# BMS-Sch.net
KiCad netlist of a schematic drawn in Altium Designer
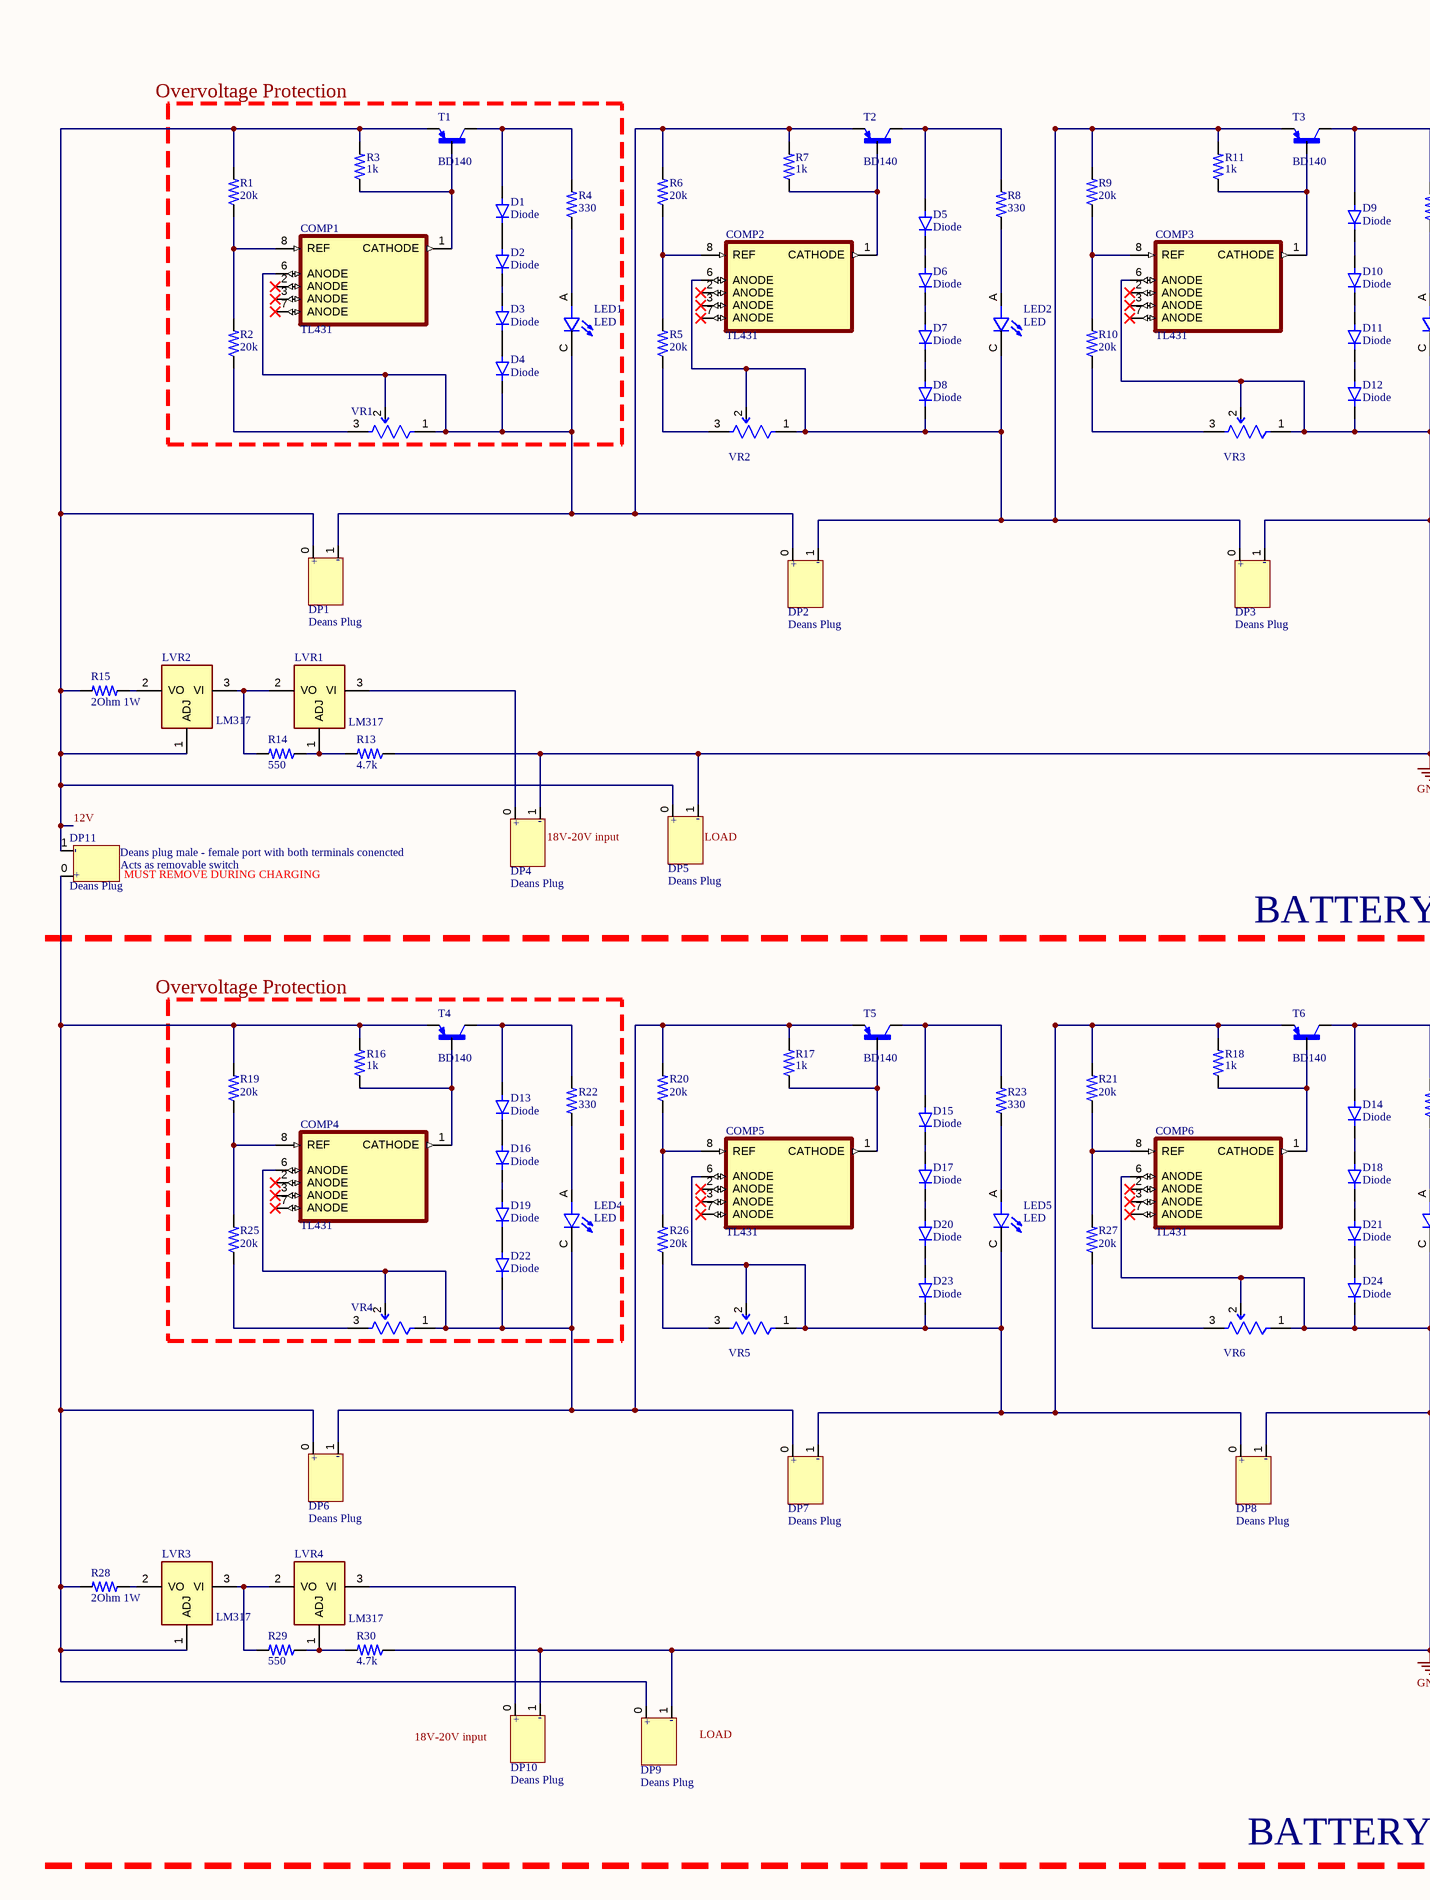
[diagram p0: BMS-Sch.SchDoc, left]
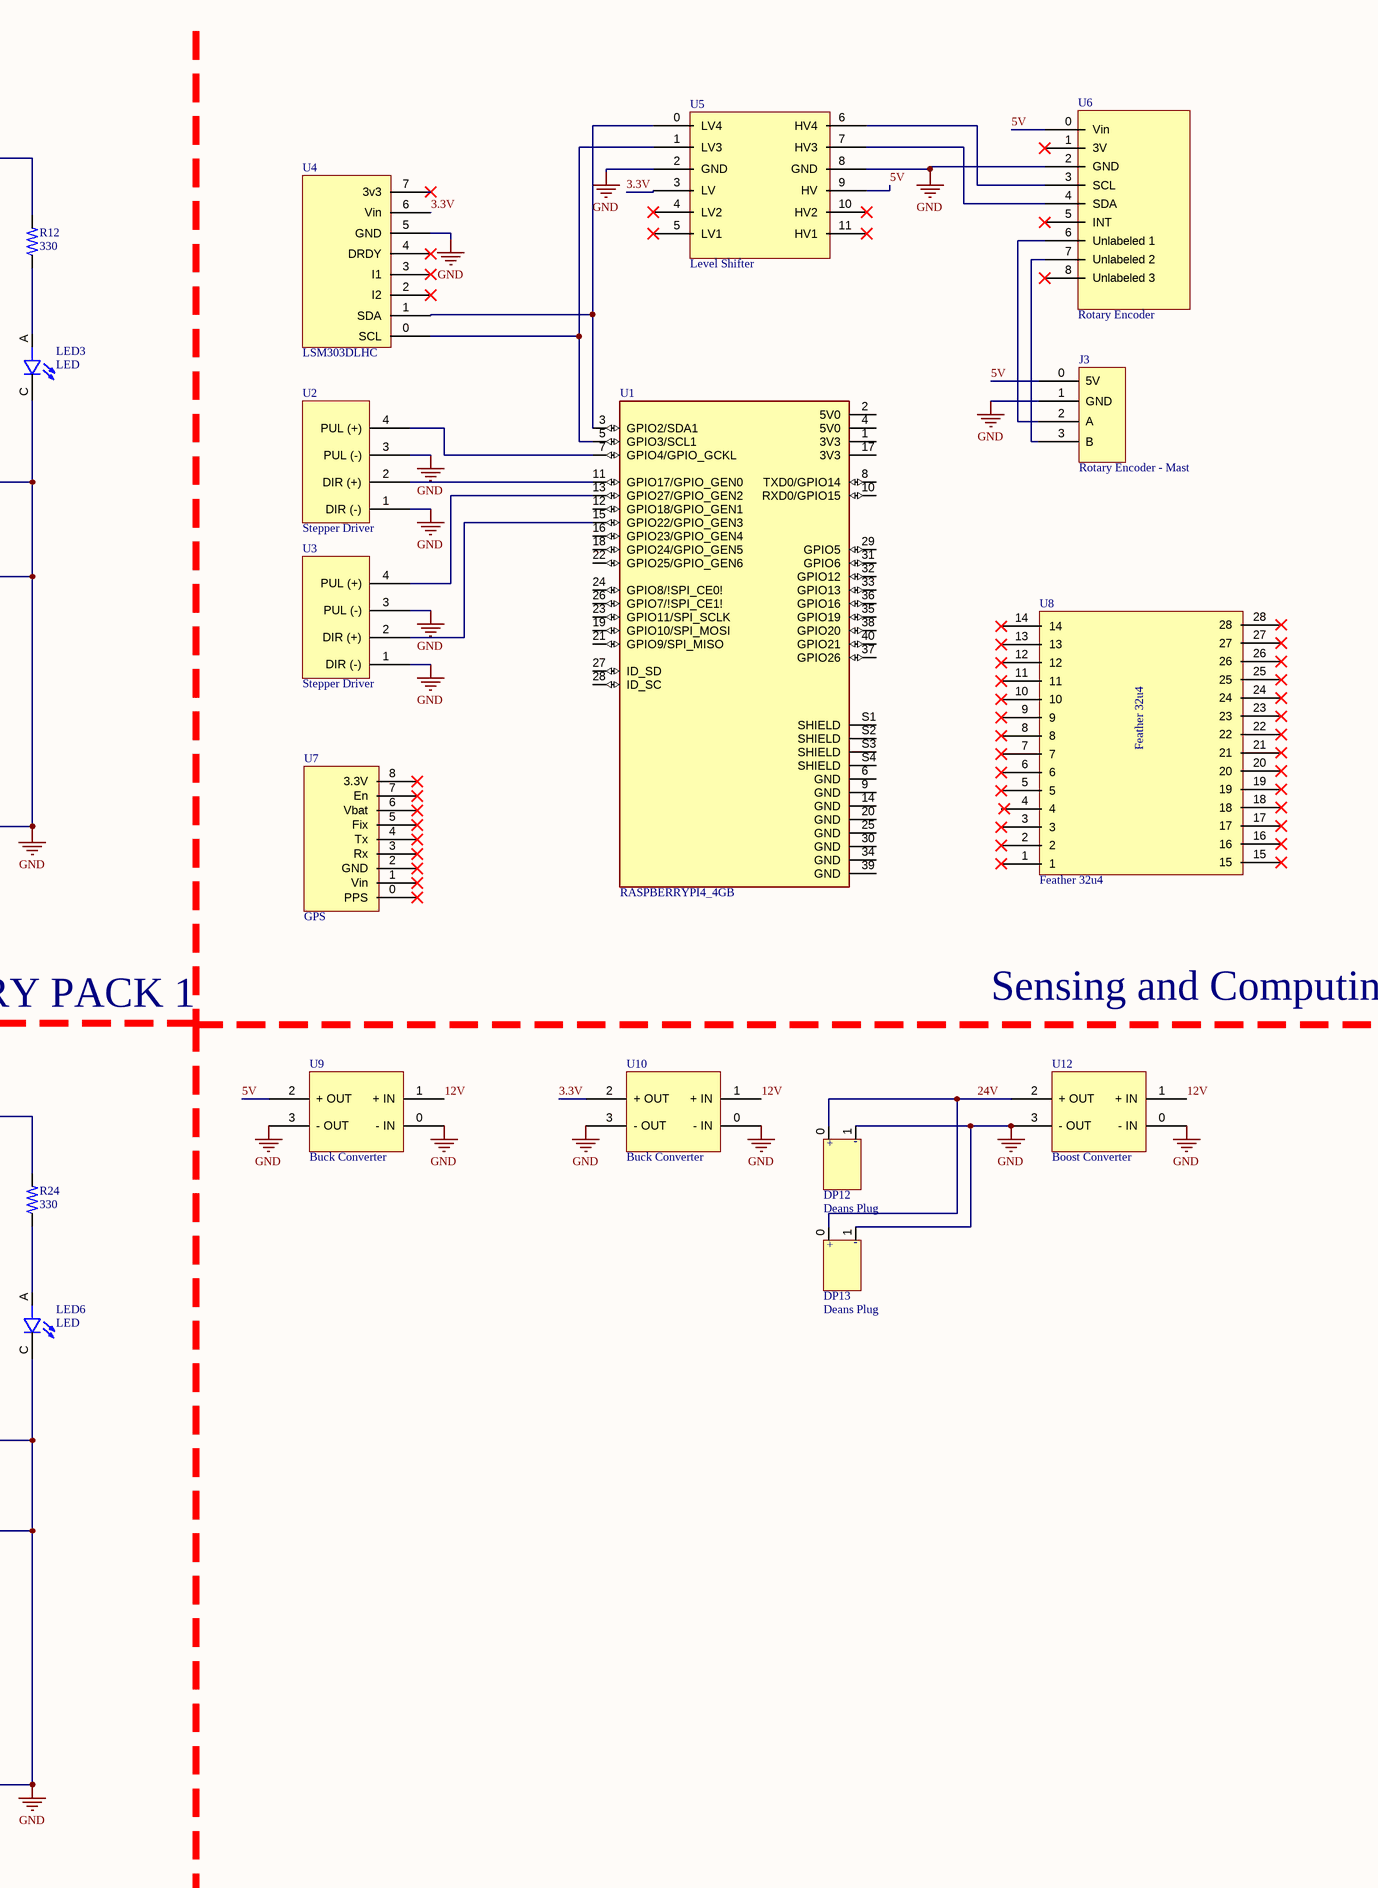
[diagram p1: BMS-Sch.SchDoc, right]

(export (version "E")
  (design (tool "Eeschema 10.0.6"))
  (components
    (comp (ref "COMP1")
      (value "TL431")
      (footprint "SOIC127P599X175-8N")
      (description "Adjustable precision shunt regulator 8-SOIC 0 to 70")
      (fields (field (name "MF") "Texas Instruments") (field (name "MP") "TL431CD"))
      (libsource (lib "Schlib") (part "TL431"))
    )
    (comp (ref "COMP2")
      (value "TL431")
      (footprint "SOIC127P599X175-8N")
      (description "Adjustable precision shunt regulator 8-SOIC 0 to 70")
      (fields (field (name "MF") "Texas Instruments") (field (name "MP") "TL431CD"))
      (libsource (lib "Schlib") (part "TL431"))
    )
    (comp (ref "COMP3")
      (value "TL431")
      (footprint "SOIC127P599X175-8N")
      (description "Adjustable precision shunt regulator 8-SOIC 0 to 70")
      (fields (field (name "MF") "Texas Instruments") (field (name "MP") "TL431CD"))
      (libsource (lib "Schlib") (part "TL431"))
    )
    (comp (ref "COMP4")
      (value "TL431")
      (footprint "SOIC127P599X175-8N")
      (description "Adjustable precision shunt regulator 8-SOIC 0 to 70")
      (fields (field (name "MF") "Texas Instruments") (field (name "MP") "TL431CD"))
      (libsource (lib "Schlib") (part "TL431"))
    )
    (comp (ref "COMP5")
      (value "TL431")
      (footprint "SOIC127P599X175-8N")
      (description "Adjustable precision shunt regulator 8-SOIC 0 to 70")
      (fields (field (name "MF") "Texas Instruments") (field (name "MP") "TL431CD"))
      (libsource (lib "Schlib") (part "TL431"))
    )
    (comp (ref "COMP6")
      (value "TL431")
      (footprint "SOIC127P599X175-8N")
      (description "Adjustable precision shunt regulator 8-SOIC 0 to 70")
      (fields (field (name "MF") "Texas Instruments") (field (name "MP") "TL431CD"))
      (libsource (lib "Schlib") (part "TL431"))
    )
    (comp (ref "D1")
      (value "Diode")
      (footprint "DIOAD1060W80L520D270")
      (description "Diode Standard 1000V 1A Through Hole DO-204AL _DO-41_")
      (fields (field (name "MF") "ON Semiconductor") (field (name "MP") "1N4007"))
      (libsource (lib "Schlib") (part "Diode"))
    )
    (comp (ref "D2")
      (value "Diode")
      (footprint "DIOAD1060W80L520D270")
      (description "Diode Standard 1000V 1A Through Hole DO-204AL _DO-41_")
      (fields (field (name "MF") "ON Semiconductor") (field (name "MP") "1N4007"))
      (libsource (lib "Schlib") (part "Diode"))
    )
    (comp (ref "D3")
      (value "Diode")
      (footprint "DIOAD1060W80L520D270")
      (description "Diode Standard 1000V 1A Through Hole DO-204AL _DO-41_")
      (fields (field (name "MF") "ON Semiconductor") (field (name "MP") "1N4007"))
      (libsource (lib "Schlib") (part "Diode"))
    )
    (comp (ref "D4")
      (value "Diode")
      (footprint "DIOAD1060W80L520D270")
      (description "Diode Standard 1000V 1A Through Hole DO-204AL _DO-41_")
      (fields (field (name "MF") "ON Semiconductor") (field (name "MP") "1N4007"))
      (libsource (lib "Schlib") (part "Diode"))
    )
    (comp (ref "D5")
      (value "Diode")
      (footprint "DIOAD1060W80L520D270")
      (description "Diode Standard 1000V 1A Through Hole DO-204AL _DO-41_")
      (fields (field (name "MF") "ON Semiconductor") (field (name "MP") "1N4007"))
      (libsource (lib "Schlib") (part "Diode"))
    )
    (comp (ref "D6")
      (value "Diode")
      (footprint "DIOAD1060W80L520D270")
      (description "Diode Standard 1000V 1A Through Hole DO-204AL _DO-41_")
      (fields (field (name "MF") "ON Semiconductor") (field (name "MP") "1N4007"))
      (libsource (lib "Schlib") (part "Diode"))
    )
    (comp (ref "D7")
      (value "Diode")
      (footprint "DIOAD1060W80L520D270")
      (description "Diode Standard 1000V 1A Through Hole DO-204AL _DO-41_")
      (fields (field (name "MF") "ON Semiconductor") (field (name "MP") "1N4007"))
      (libsource (lib "Schlib") (part "Diode"))
    )
    (comp (ref "D8")
      (value "Diode")
      (footprint "DIOAD1060W80L520D270")
      (description "Diode Standard 1000V 1A Through Hole DO-204AL _DO-41_")
      (fields (field (name "MF") "ON Semiconductor") (field (name "MP") "1N4007"))
      (libsource (lib "Schlib") (part "Diode"))
    )
    (comp (ref "D9")
      (value "Diode")
      (footprint "DIOAD1060W80L520D270")
      (description "Diode Standard 1000V 1A Through Hole DO-204AL _DO-41_")
      (fields (field (name "MF") "ON Semiconductor") (field (name "MP") "1N4007"))
      (libsource (lib "Schlib") (part "Diode"))
    )
    (comp (ref "D10")
      (value "Diode")
      (footprint "DIOAD1060W80L520D270")
      (description "Diode Standard 1000V 1A Through Hole DO-204AL _DO-41_")
      (fields (field (name "MF") "ON Semiconductor") (field (name "MP") "1N4007"))
      (libsource (lib "Schlib") (part "Diode"))
    )
    (comp (ref "D11")
      (value "Diode")
      (footprint "DIOAD1060W80L520D270")
      (description "Diode Standard 1000V 1A Through Hole DO-204AL _DO-41_")
      (fields (field (name "MF") "ON Semiconductor") (field (name "MP") "1N4007"))
      (libsource (lib "Schlib") (part "Diode"))
    )
    (comp (ref "D12")
      (value "Diode")
      (footprint "DIOAD1060W80L520D270")
      (description "Diode Standard 1000V 1A Through Hole DO-204AL _DO-41_")
      (fields (field (name "MF") "ON Semiconductor") (field (name "MP") "1N4007"))
      (libsource (lib "Schlib") (part "Diode"))
    )
    (comp (ref "D13")
      (value "Diode")
      (footprint "DIOAD1060W80L520D270")
      (description "Diode Standard 1000V 1A Through Hole DO-204AL _DO-41_")
      (fields (field (name "MF") "ON Semiconductor") (field (name "MP") "1N4007"))
      (libsource (lib "Schlib") (part "Diode"))
    )
    (comp (ref "D14")
      (value "Diode")
      (footprint "DIOAD1060W80L520D270")
      (description "Diode Standard 1000V 1A Through Hole DO-204AL _DO-41_")
      (fields (field (name "MF") "ON Semiconductor") (field (name "MP") "1N4007"))
      (libsource (lib "Schlib") (part "Diode"))
    )
    (comp (ref "D15")
      (value "Diode")
      (footprint "DIOAD1060W80L520D270")
      (description "Diode Standard 1000V 1A Through Hole DO-204AL _DO-41_")
      (fields (field (name "MF") "ON Semiconductor") (field (name "MP") "1N4007"))
      (libsource (lib "Schlib") (part "Diode"))
    )
    (comp (ref "D16")
      (value "Diode")
      (footprint "DIOAD1060W80L520D270")
      (description "Diode Standard 1000V 1A Through Hole DO-204AL _DO-41_")
      (fields (field (name "MF") "ON Semiconductor") (field (name "MP") "1N4007"))
      (libsource (lib "Schlib") (part "Diode"))
    )
    (comp (ref "D17")
      (value "Diode")
      (footprint "DIOAD1060W80L520D270")
      (description "Diode Standard 1000V 1A Through Hole DO-204AL _DO-41_")
      (fields (field (name "MF") "ON Semiconductor") (field (name "MP") "1N4007"))
      (libsource (lib "Schlib") (part "Diode"))
    )
    (comp (ref "D18")
      (value "Diode")
      (footprint "DIOAD1060W80L520D270")
      (description "Diode Standard 1000V 1A Through Hole DO-204AL _DO-41_")
      (fields (field (name "MF") "ON Semiconductor") (field (name "MP") "1N4007"))
      (libsource (lib "Schlib") (part "Diode"))
    )
    (comp (ref "D19")
      (value "Diode")
      (footprint "DIOAD1060W80L520D270")
      (description "Diode Standard 1000V 1A Through Hole DO-204AL _DO-41_")
      (fields (field (name "MF") "ON Semiconductor") (field (name "MP") "1N4007"))
      (libsource (lib "Schlib") (part "Diode"))
    )
    (comp (ref "D20")
      (value "Diode")
      (footprint "DIOAD1060W80L520D270")
      (description "Diode Standard 1000V 1A Through Hole DO-204AL _DO-41_")
      (fields (field (name "MF") "ON Semiconductor") (field (name "MP") "1N4007"))
      (libsource (lib "Schlib") (part "Diode"))
    )
    (comp (ref "D21")
      (value "Diode")
      (footprint "DIOAD1060W80L520D270")
      (description "Diode Standard 1000V 1A Through Hole DO-204AL _DO-41_")
      (fields (field (name "MF") "ON Semiconductor") (field (name "MP") "1N4007"))
      (libsource (lib "Schlib") (part "Diode"))
    )
    (comp (ref "D22")
      (value "Diode")
      (footprint "DIOAD1060W80L520D270")
      (description "Diode Standard 1000V 1A Through Hole DO-204AL _DO-41_")
      (fields (field (name "MF") "ON Semiconductor") (field (name "MP") "1N4007"))
      (libsource (lib "Schlib") (part "Diode"))
    )
    (comp (ref "D23")
      (value "Diode")
      (footprint "DIOAD1060W80L520D270")
      (description "Diode Standard 1000V 1A Through Hole DO-204AL _DO-41_")
      (fields (field (name "MF") "ON Semiconductor") (field (name "MP") "1N4007"))
      (libsource (lib "Schlib") (part "Diode"))
    )
    (comp (ref "D24")
      (value "Diode")
      (footprint "DIOAD1060W80L520D270")
      (description "Diode Standard 1000V 1A Through Hole DO-204AL _DO-41_")
      (fields (field (name "MF") "ON Semiconductor") (field (name "MP") "1N4007"))
      (libsource (lib "Schlib") (part "Diode"))
    )
    (comp (ref "DP1")
      (value "Deans Plug")
      (footprint "Deans Connector")
      (libsource (lib "Schlib") (part "Deans Plug"))
    )
    (comp (ref "DP2")
      (value "Deans Plug")
      (footprint "Deans Connector")
      (libsource (lib "Schlib") (part "Deans Plug"))
    )
    (comp (ref "DP3")
      (value "Deans Plug")
      (footprint "Deans Connector")
      (libsource (lib "Schlib") (part "Deans Plug"))
    )
    (comp (ref "DP4")
      (value "Deans Plug")
      (footprint "Deans Connector")
      (libsource (lib "Schlib") (part "Deans Plug"))
    )
    (comp (ref "DP5")
      (value "Deans Plug")
      (footprint "Deans Connector")
      (libsource (lib "Schlib") (part "Deans Plug"))
    )
    (comp (ref "DP6")
      (value "Deans Plug")
      (footprint "Deans Connector")
      (libsource (lib "Schlib") (part "Deans Plug"))
    )
    (comp (ref "DP7")
      (value "Deans Plug")
      (footprint "Deans Connector")
      (libsource (lib "Schlib") (part "Deans Plug"))
    )
    (comp (ref "DP8")
      (value "Deans Plug")
      (footprint "Deans Connector")
      (libsource (lib "Schlib") (part "Deans Plug"))
    )
    (comp (ref "DP9")
      (value "Deans Plug")
      (footprint "Deans Connector")
      (libsource (lib "Schlib") (part "Deans Plug"))
    )
    (comp (ref "DP10")
      (value "Deans Plug")
      (footprint "Deans Connector")
      (libsource (lib "Schlib") (part "Deans Plug"))
    )
    (comp (ref "DP11")
      (value "Deans Plug")
      (footprint "Deans Connector")
      (libsource (lib "") (part "Deans Plug_1"))
    )
    (comp (ref "DP12")
      (value "Deans Plug")
      (footprint "Deans Connector")
      (libsource (lib "BMSPCB") (part "Deans Plug"))
    )
    (comp (ref "DP13")
      (value "Deans Plug")
      (footprint "Deans Connector")
      (libsource (lib "BMSPCB") (part "Deans Plug"))
    )
    (comp (ref "J3")
      (value "Rotary Encoder - Mast")
      (footprint "Rotary Encoder - Mast")
      (libsource (lib "BMSPCB") (part "Rotary Encoder - Mast"))
    )
    (comp (ref "LED1")
      (value "LED")
      (footprint "LED_151054RS03000")
      (description "Red 623nm LED Indication - Discrete 1.9V Radial")
      (fields (field (name "MF") "Wurth Electronics") (field (name "MP") "151054RS03000"))
      (libsource (lib "Schlib") (part "LED"))
    )
    (comp (ref "LED2")
      (value "LED")
      (footprint "LED_151054RS03000")
      (description "Red 623nm LED Indication - Discrete 1.9V Radial")
      (fields (field (name "MF") "Wurth Electronics") (field (name "MP") "151054RS03000"))
      (libsource (lib "Schlib") (part "LED"))
    )
    (comp (ref "LED3")
      (value "LED")
      (footprint "LED_151054RS03000")
      (description "Red 623nm LED Indication - Discrete 1.9V Radial")
      (fields (field (name "MF") "Wurth Electronics") (field (name "MP") "151054RS03000"))
      (libsource (lib "Schlib") (part "LED"))
    )
    (comp (ref "LED4")
      (value "LED")
      (footprint "LED_151054RS03000")
      (description "Red 623nm LED Indication - Discrete 1.9V Radial")
      (fields (field (name "MF") "Wurth Electronics") (field (name "MP") "151054RS03000"))
      (libsource (lib "Schlib") (part "LED"))
    )
    (comp (ref "LED5")
      (value "LED")
      (footprint "LED_151054RS03000")
      (description "Red 623nm LED Indication - Discrete 1.9V Radial")
      (fields (field (name "MF") "Wurth Electronics") (field (name "MP") "151054RS03000"))
      (libsource (lib "Schlib") (part "LED"))
    )
    (comp (ref "LED6")
      (value "LED")
      (footprint "LED_151054RS03000")
      (description "Red 623nm LED Indication - Discrete 1.9V Radial")
      (fields (field (name "MF") "Wurth Electronics") (field (name "MP") "151054RS03000"))
      (libsource (lib "Schlib") (part "LED"))
    )
    (comp (ref "LVR1")
      (value "LM317")
      (footprint "TO245P780X300X1364-3")
      (description "Linear Voltage Regulator IC 1 Output 100mA SOT-89-3")
      (fields (field (name "MF") "ON Semiconductor"))
      (libsource (lib "SnapEDAsch") (part "LM317"))
    )
    (comp (ref "LVR2")
      (value "LM317")
      (footprint "TO245P780X300X1364-3")
      (description "Linear Voltage Regulator IC 1 Output 100mA SOT-89-3")
      (fields (field (name "MF") "ON Semiconductor"))
      (libsource (lib "SnapEDAsch") (part "LM317"))
    )
    (comp (ref "LVR3")
      (value "LM317")
      (footprint "TO245P780X300X1364-3")
      (description "Linear Voltage Regulator IC 1 Output 100mA SOT-89-3")
      (fields (field (name "MF") "ON Semiconductor"))
      (libsource (lib "SnapEDAsch") (part "LM317"))
    )
    (comp (ref "LVR4")
      (value "LM317")
      (footprint "TO245P780X300X1364-3")
      (description "Linear Voltage Regulator IC 1 Output 100mA SOT-89-3")
      (fields (field (name "MF") "ON Semiconductor"))
      (libsource (lib "SnapEDAsch") (part "LM317"))
    )
    (comp (ref "R1")
      (value "20k")
      (footprint "RESC2012X65N")
      (description "RES 20k OHM 1% 1/4W 0805")
      (fields (field (name "MF") "TE Connectivity") (field (name "TOLERANCE") "1%"))
      (libsource (lib "Schlib") (part "Resistor"))
    )
    (comp (ref "R2")
      (value "20k")
      (footprint "RESC2012X65N")
      (description "RES 20k OHM 1% 1/4W 0805")
      (fields (field (name "MF") "TE Connectivity") (field (name "TOLERANCE") "1%"))
      (libsource (lib "Schlib") (part "Resistor"))
    )
    (comp (ref "R3")
      (value "1k")
      (footprint "RESC2012X65N")
      (description "RES 1k OHM 1% 1/4W 0805")
      (fields (field (name "MF") "TE Connectivity") (field (name "TOLERANCE") "1%"))
      (libsource (lib "Schlib") (part "Resistor"))
    )
    (comp (ref "R4")
      (value "330")
      (footprint "RESC2012X65N")
      (description "RES 330 OHM 1% 1/4W 0805")
      (fields (field (name "MF") "TE Connectivity") (field (name "TOLERANCE") "1%"))
      (libsource (lib "Schlib") (part "Resistor"))
    )
    (comp (ref "R5")
      (value "20k")
      (footprint "RESC2012X65N")
      (description "RES 20k OHM 1% 1/4W 0805")
      (fields (field (name "MF") "TE Connectivity") (field (name "TOLERANCE") "1%"))
      (libsource (lib "Schlib") (part "Resistor"))
    )
    (comp (ref "R6")
      (value "20k")
      (footprint "RESC2012X65N")
      (description "RES 20k OHM 1% 1/4W 0805")
      (fields (field (name "MF") "TE Connectivity") (field (name "TOLERANCE") "1%"))
      (libsource (lib "Schlib") (part "Resistor"))
    )
    (comp (ref "R7")
      (value "1k")
      (footprint "RESC2012X65N")
      (description "RES 1k OHM 1% 1/4W 0805")
      (fields (field (name "MF") "TE Connectivity") (field (name "TOLERANCE") "1%"))
      (libsource (lib "Schlib") (part "Resistor"))
    )
    (comp (ref "R8")
      (value "330")
      (footprint "RESC2012X65N")
      (description "RES 330 OHM 1% 1/4W 0805")
      (fields (field (name "MF") "TE Connectivity") (field (name "TOLERANCE") "1%"))
      (libsource (lib "Schlib") (part "Resistor"))
    )
    (comp (ref "R9")
      (value "20k")
      (footprint "RESC2012X65N")
      (description "RES 20k OHM 1% 1/4W 0805")
      (fields (field (name "MF") "TE Connectivity") (field (name "TOLERANCE") "1%"))
      (libsource (lib "Schlib") (part "Resistor"))
    )
    (comp (ref "R10")
      (value "20k")
      (footprint "RESC2012X65N")
      (description "RES 20k OHM 1% 1/4W 0805")
      (fields (field (name "MF") "TE Connectivity") (field (name "TOLERANCE") "1%"))
      (libsource (lib "Schlib") (part "Resistor"))
    )
    (comp (ref "R11")
      (value "1k")
      (footprint "RESC2012X65N")
      (description "RES 1k OHM 1% 1/4W 0805")
      (fields (field (name "MF") "TE Connectivity") (field (name "TOLERANCE") "1%"))
      (libsource (lib "Schlib") (part "Resistor"))
    )
    (comp (ref "R12")
      (value "330")
      (footprint "RESC2012X65N")
      (description "RES 330 OHM 1% 1/4W 0805")
      (fields (field (name "MF") "TE Connectivity") (field (name "TOLERANCE") "1%"))
      (libsource (lib "Schlib") (part "Resistor"))
    )
    (comp (ref "R13")
      (value "4.7k")
      (footprint "RESC2012X65N")
      (description "RES 4.7k OHM 1% 1/4W 0805")
      (fields (field (name "MF") "TE Connectivity") (field (name "TOLERANCE") "1%"))
      (libsource (lib "Schlib") (part "Resistor"))
    )
    (comp (ref "R14")
      (value "550")
      (footprint "RESC2012X65N")
      (description "RES 550 OHM 1% 1/4W 0805")
      (fields (field (name "MF") "TE Connectivity") (field (name "TOLERANCE") "1%"))
      (libsource (lib "Schlib") (part "Resistor"))
    )
    (comp (ref "R15")
      (value "2Ohm 1W")
      (footprint "RESC2012X65N")
      (description "RES 2 OHM 1% 1/4W 0805")
      (fields (field (name "MF") "TE Connectivity") (field (name "TOLERANCE") "1%"))
      (libsource (lib "Schlib") (part "Resistor"))
    )
    (comp (ref "R16")
      (value "1k")
      (footprint "RESC2012X65N")
      (description "RES 1k OHM 1% 1/4W 0805")
      (fields (field (name "MF") "TE Connectivity") (field (name "TOLERANCE") "1%"))
      (libsource (lib "Schlib") (part "Resistor"))
    )
    (comp (ref "R17")
      (value "1k")
      (footprint "RESC2012X65N")
      (description "RES 1k OHM 1% 1/4W 0805")
      (fields (field (name "MF") "TE Connectivity") (field (name "TOLERANCE") "1%"))
      (libsource (lib "Schlib") (part "Resistor"))
    )
    (comp (ref "R18")
      (value "1k")
      (footprint "RESC2012X65N")
      (description "RES 1k OHM 1% 1/4W 0805")
      (fields (field (name "MF") "TE Connectivity") (field (name "TOLERANCE") "1%"))
      (libsource (lib "Schlib") (part "Resistor"))
    )
    (comp (ref "R19")
      (value "20k")
      (footprint "RESC2012X65N")
      (description "RES 20k OHM 1% 1/4W 0805")
      (fields (field (name "MF") "TE Connectivity") (field (name "TOLERANCE") "1%"))
      (libsource (lib "Schlib") (part "Resistor"))
    )
    (comp (ref "R20")
      (value "20k")
      (footprint "RESC2012X65N")
      (description "RES 20k OHM 1% 1/4W 0805")
      (fields (field (name "MF") "TE Connectivity") (field (name "TOLERANCE") "1%"))
      (libsource (lib "Schlib") (part "Resistor"))
    )
    (comp (ref "R21")
      (value "20k")
      (footprint "RESC2012X65N")
      (description "RES 20k OHM 1% 1/4W 0805")
      (fields (field (name "MF") "TE Connectivity") (field (name "TOLERANCE") "1%"))
      (libsource (lib "Schlib") (part "Resistor"))
    )
    (comp (ref "R22")
      (value "330")
      (footprint "RESC2012X65N")
      (description "RES 330 OHM 1% 1/4W 0805")
      (fields (field (name "MF") "TE Connectivity") (field (name "TOLERANCE") "1%"))
      (libsource (lib "Schlib") (part "Resistor"))
    )
    (comp (ref "R23")
      (value "330")
      (footprint "RESC2012X65N")
      (description "RES 330 OHM 1% 1/4W 0805")
      (fields (field (name "MF") "TE Connectivity") (field (name "TOLERANCE") "1%"))
      (libsource (lib "Schlib") (part "Resistor"))
    )
    (comp (ref "R24")
      (value "330")
      (footprint "RESC2012X65N")
      (description "RES 330 OHM 1% 1/4W 0805")
      (fields (field (name "MF") "TE Connectivity") (field (name "TOLERANCE") "1%"))
      (libsource (lib "Schlib") (part "Resistor"))
    )
    (comp (ref "R25")
      (value "20k")
      (footprint "RESC2012X65N")
      (description "RES 20k OHM 1% 1/4W 0805")
      (fields (field (name "MF") "TE Connectivity") (field (name "TOLERANCE") "1%"))
      (libsource (lib "Schlib") (part "Resistor"))
    )
    (comp (ref "R26")
      (value "20k")
      (footprint "RESC2012X65N")
      (description "RES 20k OHM 1% 1/4W 0805")
      (fields (field (name "MF") "TE Connectivity") (field (name "TOLERANCE") "1%"))
      (libsource (lib "Schlib") (part "Resistor"))
    )
    (comp (ref "R27")
      (value "20k")
      (footprint "RESC2012X65N")
      (description "RES 20k OHM 1% 1/4W 0805")
      (fields (field (name "MF") "TE Connectivity") (field (name "TOLERANCE") "1%"))
      (libsource (lib "Schlib") (part "Resistor"))
    )
    (comp (ref "R28")
      (value "2Ohm 1W")
      (footprint "RESC2012X65N")
      (description "RES 2 OHM 1% 1/4W 0805")
      (fields (field (name "MF") "TE Connectivity") (field (name "TOLERANCE") "1%"))
      (libsource (lib "Schlib") (part "Resistor"))
    )
    (comp (ref "R29")
      (value "550")
      (footprint "RESC2012X65N")
      (description "RES 550 OHM 1% 1/4W 0805")
      (fields (field (name "MF") "TE Connectivity") (field (name "TOLERANCE") "1%"))
      (libsource (lib "Schlib") (part "Resistor"))
    )
    (comp (ref "R30")
      (value "4.7k")
      (footprint "RESC2012X65N")
      (description "RES 4.7k OHM 1% 1/4W 0805")
      (fields (field (name "MF") "TE Connectivity") (field (name "TOLERANCE") "1%"))
      (libsource (lib "Schlib") (part "Resistor"))
    )
    (comp (ref "T1")
      (value "BD140")
      (footprint "TO245P780X300X1364-3")
      (description "Bipolar _BJT_ Transistor PNP 80V 1.5A 1.25W Through Hole SOT-32-3")
      (fields (field (name "MF") "STMicroelectronics"))
      (libsource (lib "Schlib") (part "BD140"))
    )
    (comp (ref "T2")
      (value "BD140")
      (footprint "TO245P780X300X1364-3")
      (description "Bipolar _BJT_ Transistor PNP 80V 1.5A 1.25W Through Hole SOT-32-3")
      (fields (field (name "MF") "STMicroelectronics"))
      (libsource (lib "Schlib") (part "BD140"))
    )
    (comp (ref "T3")
      (value "BD140")
      (footprint "TO245P780X300X1364-3")
      (description "Bipolar _BJT_ Transistor PNP 80V 1.5A 1.25W Through Hole SOT-32-3")
      (fields (field (name "MF") "STMicroelectronics"))
      (libsource (lib "Schlib") (part "BD140"))
    )
    (comp (ref "T4")
      (value "BD140")
      (footprint "TO245P780X300X1364-3")
      (description "Bipolar _BJT_ Transistor PNP 80V 1.5A 1.25W Through Hole SOT-32-3")
      (fields (field (name "MF") "STMicroelectronics"))
      (libsource (lib "Schlib") (part "BD140"))
    )
    (comp (ref "T5")
      (value "BD140")
      (footprint "TO245P780X300X1364-3")
      (description "Bipolar _BJT_ Transistor PNP 80V 1.5A 1.25W Through Hole SOT-32-3")
      (fields (field (name "MF") "STMicroelectronics"))
      (libsource (lib "Schlib") (part "BD140"))
    )
    (comp (ref "T6")
      (value "BD140")
      (footprint "TO245P780X300X1364-3")
      (description "Bipolar _BJT_ Transistor PNP 80V 1.5A 1.25W Through Hole SOT-32-3")
      (fields (field (name "MF") "STMicroelectronics"))
      (libsource (lib "Schlib") (part "BD140"))
    )
    (comp (ref "U1")
      (value "RASPBERRYPI4_4GB")
      (footprint "RPi Pad")
      (description "BCM2711 Raspberry Pi 4 Model B 4GB - ARMÂ® CortexÂ®-A72 MPU Embedded Evaluation Board")
      (fields (field (name "MF") "Raspberry Pi Foundation (NF)") (field (name "MP") "RASPBERRYPI4 4GB"))
      (libsource (lib "BMSPCB") (part "RASPBERRYPI4_4GB"))
    )
    (comp (ref "U2")
      (value "Stepper Driver")
      (footprint "STEPPER DRIVER Pad")
      (libsource (lib "BMSPCB") (part "Stepper Driver"))
    )
    (comp (ref "U3")
      (value "Stepper Driver")
      (footprint "STEPPER DRIVER Pad")
      (libsource (lib "BMSPCB") (part "Stepper Driver"))
    )
    (comp (ref "U4")
      (value "LSM303DLHC")
      (footprint "COMPASS PAD")
      (libsource (lib "BMSPCB") (part "LSM303DLHC"))
    )
    (comp (ref "U5")
      (value "Level Shifter")
      (footprint "LEVEL SHIFTER PAD")
      (libsource (lib "BMSPCB") (part "Level Shifter"))
    )
    (comp (ref "U6")
      (value "Rotary Encoder")
      (footprint "ROTARY ENCODER - Hull")
      (libsource (lib "BMSPCB") (part "Rotary Encoder"))
    )
    (comp (ref "U7") (value "GPS") (footprint "GPS Pad") (libsource (lib "BMSPCB") (part "GPS")))
    (comp (ref "U8")
      (value "Feather 32u4")
      (footprint "LoRa PAD")
      (libsource (lib "BMSPCB") (part "Feather 32u4"))
    )
    (comp (ref "U9")
      (value "Buck Converter")
      (footprint "BUCK Pad")
      (libsource (lib "BMSPCB") (part "Buck Converter"))
    )
    (comp (ref "U10")
      (value "Buck Converter")
      (footprint "BUCK Pad")
      (libsource (lib "BMSPCB") (part "Buck Converter"))
    )
    (comp (ref "U12")
      (value "Boost Converter")
      (footprint "Boost Pad")
      (libsource (lib "BMSPCB") (part "Boost Converter"))
    )
    (comp (ref "VR1")
      (value "Res_Bourns_3296W-1-502LF_eec")
      (footprint "Bourns_3296W-1-502LF_0")
      (description "RES TRIMMER 5K OHM 0.5W PC PIN")
      (fields (field (name "PART NUMBER") "3296W-1-502LF") (field (name "MANUFACTURER") "Bourns"))
      (libsource (lib "Schlib") (part "Res_Bourns_3296W-1-502LF_eec"))
    )
    (comp (ref "VR2")
      (value "Res_Bourns_3296W-1-502LF_eec")
      (footprint "Bourns_3296W-1-502LF_0")
      (description "RES TRIMMER 5K OHM 0.5W PC PIN")
      (fields (field (name "PART NUMBER") "3296W-1-502LF") (field (name "MANUFACTURER") "Bourns"))
      (libsource (lib "Schlib") (part "Res_Bourns_3296W-1-502LF_eec"))
    )
    (comp (ref "VR3")
      (value "Res_Bourns_3296W-1-502LF_eec")
      (footprint "Bourns_3296W-1-502LF_0")
      (description "RES TRIMMER 5K OHM 0.5W PC PIN")
      (fields (field (name "PART NUMBER") "3296W-1-502LF") (field (name "MANUFACTURER") "Bourns"))
      (libsource (lib "Schlib") (part "Res_Bourns_3296W-1-502LF_eec"))
    )
    (comp (ref "VR4")
      (value "Res_Bourns_3296W-1-502LF_eec")
      (footprint "Bourns_3296W-1-502LF_0")
      (description "RES TRIMMER 5K OHM 0.5W PC PIN")
      (fields (field (name "PART NUMBER") "3296W-1-502LF") (field (name "MANUFACTURER") "Bourns"))
      (libsource (lib "Schlib") (part "Res_Bourns_3296W-1-502LF_eec"))
    )
    (comp (ref "VR5")
      (value "Res_Bourns_3296W-1-502LF_eec")
      (footprint "Bourns_3296W-1-502LF_0")
      (description "RES TRIMMER 5K OHM 0.5W PC PIN")
      (fields (field (name "PART NUMBER") "3296W-1-502LF") (field (name "MANUFACTURER") "Bourns"))
      (libsource (lib "Schlib") (part "Res_Bourns_3296W-1-502LF_eec"))
    )
    (comp (ref "VR6")
      (value "Res_Bourns_3296W-1-502LF_eec")
      (footprint "Bourns_3296W-1-502LF_0")
      (description "RES TRIMMER 5K OHM 0.5W PC PIN")
      (fields (field (name "PART NUMBER") "3296W-1-502LF") (field (name "MANUFACTURER") "Bourns"))
      (libsource (lib "Schlib") (part "Res_Bourns_3296W-1-502LF_eec"))
    )
  )
  (nets
    (net (code "1") (name "/3.3V") (class "Default")
      (node (ref "U10") (pin "2") (pinfunction "+_OUT_2") (pintype "passive"))
      (node (ref "U4") (pin "6") (pinfunction "Vin_6") (pintype "passive"))
      (node (ref "U5") (pin "3") (pinfunction "LV_3") (pintype "passive"))
    )
    (net (code "2") (name "/5V") (class "Default")
      (node (ref "J3") (pin "0") (pinfunction "5V_0") (pintype "passive"))
      (node (ref "U5") (pin "9") (pinfunction "HV_9") (pintype "passive"))
      (node (ref "U6") (pin "0") (pinfunction "Vin_0") (pintype "passive"))
      (node (ref "U9") (pin "2") (pinfunction "+_OUT_2") (pintype "passive"))
    )
    (net (code "3") (name "/12V") (class "Default")
      (node (ref "DP1") (pin "0") (pinfunction "0_0") (pintype "passive"))
      (node (ref "DP11") (pin "1") (pinfunction "1_1") (pintype "passive"))
      (node (ref "DP5") (pin "0") (pinfunction "0_0") (pintype "passive"))
      (node (ref "LVR2") (pin "1") (pinfunction "ADJ_1") (pintype "power_in"))
      (node (ref "R1") (pin "2") (pinfunction "2_2") (pintype "passive"))
      (node (ref "R15") (pin "2") (pinfunction "2_2") (pintype "passive"))
      (node (ref "R3") (pin "2") (pinfunction "2_2") (pintype "passive"))
      (node (ref "T1") (pin "1") (pinfunction "E_1") (pintype "passive"))
      (node (ref "U10") (pin "1") (pinfunction "+_IN_1") (pintype "passive"))
      (node (ref "U12") (pin "1") (pinfunction "+_IN_1") (pintype "passive"))
      (node (ref "U9") (pin "1") (pinfunction "+_IN_1") (pintype "passive"))
    )
    (net (code "4") (name "/24V") (class "Default")
      (node (ref "DP12") (pin "0") (pinfunction "0_0") (pintype "passive"))
      (node (ref "DP13") (pin "0") (pinfunction "0_0") (pintype "passive"))
      (node (ref "U12") (pin "2") (pinfunction "+_OUT_2") (pintype "passive"))
    )
    (net (code "5") (name "GND") (class "Default")
      (node (ref "COMP3") (pin "6") (pinfunction "ANODE_6") (pintype "bidirectional"))
      (node (ref "COMP6") (pin "6") (pinfunction "ANODE_6") (pintype "bidirectional"))
      (node (ref "D12") (pin "C") (pinfunction "C_C") (pintype "passive"))
      (node (ref "D24") (pin "C") (pinfunction "C_C") (pintype "passive"))
      (node (ref "DP10") (pin "1") (pinfunction "1_1") (pintype "passive"))
      (node (ref "DP12") (pin "1") (pinfunction "1_1") (pintype "passive"))
      (node (ref "DP13") (pin "1") (pinfunction "1_1") (pintype "passive"))
      (node (ref "DP3") (pin "1") (pinfunction "1_1") (pintype "passive"))
      (node (ref "DP4") (pin "1") (pinfunction "1_1") (pintype "passive"))
      (node (ref "DP5") (pin "1") (pinfunction "1_1") (pintype "passive"))
      (node (ref "DP8") (pin "1") (pinfunction "1_1") (pintype "passive"))
      (node (ref "DP9") (pin "1") (pinfunction "1_1") (pintype "passive"))
      (node (ref "J3") (pin "1") (pinfunction "GND_1") (pintype "passive"))
      (node (ref "LED3") (pin "C") (pinfunction "C_C") (pintype "passive"))
      (node (ref "LED6") (pin "C") (pinfunction "C_C") (pintype "passive"))
      (node (ref "R13") (pin "1") (pinfunction "1_1") (pintype "passive"))
      (node (ref "R30") (pin "1") (pinfunction "1_1") (pintype "passive"))
      (node (ref "U10") (pin "0") (pinfunction "-_IN_0") (pintype "passive"))
      (node (ref "U10") (pin "3") (pinfunction "-_OUT_3") (pintype "passive"))
      (node (ref "U12") (pin "0") (pinfunction "-_IN_0") (pintype "passive"))
      (node (ref "U12") (pin "3") (pinfunction "-_OUT_3") (pintype "passive"))
      (node (ref "U2") (pin "1") (pinfunction "DIR_(-)_1") (pintype "passive"))
      (node (ref "U2") (pin "3") (pinfunction "PUL_(-)_3") (pintype "passive"))
      (node (ref "U3") (pin "1") (pinfunction "DIR_(-)_1") (pintype "passive"))
      (node (ref "U3") (pin "3") (pinfunction "PUL_(-)_3") (pintype "passive"))
      (node (ref "U4") (pin "5") (pinfunction "GND_5") (pintype "passive"))
      (node (ref "U5") (pin "2") (pinfunction "GND_2") (pintype "passive"))
      (node (ref "U5") (pin "8") (pinfunction "GND_8") (pintype "passive"))
      (node (ref "U6") (pin "2") (pinfunction "GND_2") (pintype "passive"))
      (node (ref "U9") (pin "0") (pinfunction "-_IN_0") (pintype "passive"))
      (node (ref "U9") (pin "3") (pinfunction "-_OUT_3") (pintype "passive"))
      (node (ref "VR3") (pin "1") (pinfunction "CCW_1") (pintype "passive"))
      (node (ref "VR3") (pin "2") (pinfunction "WIPER_2") (pintype "passive"))
      (node (ref "VR6") (pin "1") (pinfunction "CCW_1") (pintype "passive"))
      (node (ref "VR6") (pin "2") (pinfunction "WIPER_2") (pintype "passive"))
    )
    (net (code "6") (name "Net-(COMP1-CATHODE)") (class "Default")
      (node (ref "COMP1") (pin "1") (pinfunction "CATHODE_1") (pintype "output"))
      (node (ref "R3") (pin "1") (pinfunction "1_1") (pintype "passive"))
      (node (ref "T1") (pin "3") (pinfunction "B_3") (pintype "passive"))
    )
    (net (code "7") (name "Net-(COMP1-REF)") (class "Default")
      (node (ref "COMP1") (pin "8") (pinfunction "REF_8") (pintype "input"))
      (node (ref "R1") (pin "1") (pinfunction "1_1") (pintype "passive"))
      (node (ref "R2") (pin "2") (pinfunction "2_2") (pintype "passive"))
    )
    (net (code "8") (name "Net-(COMP2-CATHODE)") (class "Default")
      (node (ref "COMP2") (pin "1") (pinfunction "CATHODE_1") (pintype "output"))
      (node (ref "R7") (pin "1") (pinfunction "1_1") (pintype "passive"))
      (node (ref "T2") (pin "3") (pinfunction "B_3") (pintype "passive"))
    )
    (net (code "9") (name "Net-(COMP2-REF)") (class "Default")
      (node (ref "COMP2") (pin "8") (pinfunction "REF_8") (pintype "input"))
      (node (ref "R5") (pin "2") (pinfunction "2_2") (pintype "passive"))
      (node (ref "R6") (pin "1") (pinfunction "1_1") (pintype "passive"))
    )
    (net (code "10") (name "Net-(COMP3-CATHODE)") (class "Default")
      (node (ref "COMP3") (pin "1") (pinfunction "CATHODE_1") (pintype "output"))
      (node (ref "R11") (pin "1") (pinfunction "1_1") (pintype "passive"))
      (node (ref "T3") (pin "3") (pinfunction "B_3") (pintype "passive"))
    )
    (net (code "11") (name "Net-(COMP3-REF)") (class "Default")
      (node (ref "COMP3") (pin "8") (pinfunction "REF_8") (pintype "input"))
      (node (ref "R10") (pin "2") (pinfunction "2_2") (pintype "passive"))
      (node (ref "R9") (pin "1") (pinfunction "1_1") (pintype "passive"))
    )
    (net (code "12") (name "Net-(COMP4-CATHODE)") (class "Default")
      (node (ref "COMP4") (pin "1") (pinfunction "CATHODE_1") (pintype "output"))
      (node (ref "R16") (pin "1") (pinfunction "1_1") (pintype "passive"))
      (node (ref "T4") (pin "3") (pinfunction "B_3") (pintype "passive"))
    )
    (net (code "13") (name "Net-(COMP4-REF)") (class "Default")
      (node (ref "COMP4") (pin "8") (pinfunction "REF_8") (pintype "input"))
      (node (ref "R19") (pin "1") (pinfunction "1_1") (pintype "passive"))
      (node (ref "R25") (pin "2") (pinfunction "2_2") (pintype "passive"))
    )
    (net (code "14") (name "Net-(COMP5-CATHODE)") (class "Default")
      (node (ref "COMP5") (pin "1") (pinfunction "CATHODE_1") (pintype "output"))
      (node (ref "R17") (pin "1") (pinfunction "1_1") (pintype "passive"))
      (node (ref "T5") (pin "3") (pinfunction "B_3") (pintype "passive"))
    )
    (net (code "15") (name "Net-(COMP5-REF)") (class "Default")
      (node (ref "COMP5") (pin "8") (pinfunction "REF_8") (pintype "input"))
      (node (ref "R20") (pin "1") (pinfunction "1_1") (pintype "passive"))
      (node (ref "R26") (pin "2") (pinfunction "2_2") (pintype "passive"))
    )
    (net (code "16") (name "Net-(COMP6-CATHODE)") (class "Default")
      (node (ref "COMP6") (pin "1") (pinfunction "CATHODE_1") (pintype "output"))
      (node (ref "R18") (pin "1") (pinfunction "1_1") (pintype "passive"))
      (node (ref "T6") (pin "3") (pinfunction "B_3") (pintype "passive"))
    )
    (net (code "17") (name "Net-(COMP6-REF)") (class "Default")
      (node (ref "COMP6") (pin "8") (pinfunction "REF_8") (pintype "input"))
      (node (ref "R21") (pin "1") (pinfunction "1_1") (pintype "passive"))
      (node (ref "R27") (pin "2") (pinfunction "2_2") (pintype "passive"))
    )
    (net (code "18") (name "Net-(D1-PadC)") (class "Default")
      (node (ref "D1") (pin "C") (pinfunction "C_C") (pintype "passive"))
      (node (ref "D2") (pin "A") (pinfunction "A_A") (pintype "passive"))
    )
    (net (code "19") (name "Net-(D2-PadC)") (class "Default")
      (node (ref "D2") (pin "C") (pinfunction "C_C") (pintype "passive"))
      (node (ref "D3") (pin "A") (pinfunction "A_A") (pintype "passive"))
    )
    (net (code "20") (name "Net-(D3-PadC)") (class "Default")
      (node (ref "D3") (pin "C") (pinfunction "C_C") (pintype "passive"))
      (node (ref "D4") (pin "A") (pinfunction "A_A") (pintype "passive"))
    )
    (net (code "21") (name "Net-(D5-PadC)") (class "Default")
      (node (ref "D5") (pin "C") (pinfunction "C_C") (pintype "passive"))
      (node (ref "D6") (pin "A") (pinfunction "A_A") (pintype "passive"))
    )
    (net (code "22") (name "Net-(D6-PadC)") (class "Default")
      (node (ref "D6") (pin "C") (pinfunction "C_C") (pintype "passive"))
      (node (ref "D7") (pin "A") (pinfunction "A_A") (pintype "passive"))
    )
    (net (code "23") (name "Net-(D7-PadC)") (class "Default")
      (node (ref "D7") (pin "C") (pinfunction "C_C") (pintype "passive"))
      (node (ref "D8") (pin "A") (pinfunction "A_A") (pintype "passive"))
    )
    (net (code "24") (name "Net-(D10-PadA)") (class "Default")
      (node (ref "D10") (pin "A") (pinfunction "A_A") (pintype "passive"))
      (node (ref "D9") (pin "C") (pinfunction "C_C") (pintype "passive"))
    )
    (net (code "25") (name "Net-(D10-PadC)") (class "Default")
      (node (ref "D10") (pin "C") (pinfunction "C_C") (pintype "passive"))
      (node (ref "D11") (pin "A") (pinfunction "A_A") (pintype "passive"))
    )
    (net (code "26") (name "Net-(D11-PadC)") (class "Default")
      (node (ref "D11") (pin "C") (pinfunction "C_C") (pintype "passive"))
      (node (ref "D12") (pin "A") (pinfunction "A_A") (pintype "passive"))
    )
    (net (code "27") (name "Net-(D13-PadC)") (class "Default")
      (node (ref "D13") (pin "C") (pinfunction "C_C") (pintype "passive"))
      (node (ref "D16") (pin "A") (pinfunction "A_A") (pintype "passive"))
    )
    (net (code "28") (name "Net-(D14-PadC)") (class "Default")
      (node (ref "D14") (pin "C") (pinfunction "C_C") (pintype "passive"))
      (node (ref "D18") (pin "A") (pinfunction "A_A") (pintype "passive"))
    )
    (net (code "29") (name "Net-(D15-PadC)") (class "Default")
      (node (ref "D15") (pin "C") (pinfunction "C_C") (pintype "passive"))
      (node (ref "D17") (pin "A") (pinfunction "A_A") (pintype "passive"))
    )
    (net (code "30") (name "Net-(D16-PadC)") (class "Default")
      (node (ref "D16") (pin "C") (pinfunction "C_C") (pintype "passive"))
      (node (ref "D19") (pin "A") (pinfunction "A_A") (pintype "passive"))
    )
    (net (code "31") (name "Net-(D17-PadC)") (class "Default")
      (node (ref "D17") (pin "C") (pinfunction "C_C") (pintype "passive"))
      (node (ref "D20") (pin "A") (pinfunction "A_A") (pintype "passive"))
    )
    (net (code "32") (name "Net-(D18-PadC)") (class "Default")
      (node (ref "D18") (pin "C") (pinfunction "C_C") (pintype "passive"))
      (node (ref "D21") (pin "A") (pinfunction "A_A") (pintype "passive"))
    )
    (net (code "33") (name "Net-(D19-PadC)") (class "Default")
      (node (ref "D19") (pin "C") (pinfunction "C_C") (pintype "passive"))
      (node (ref "D22") (pin "A") (pinfunction "A_A") (pintype "passive"))
    )
    (net (code "34") (name "Net-(D20-PadC)") (class "Default")
      (node (ref "D20") (pin "C") (pinfunction "C_C") (pintype "passive"))
      (node (ref "D23") (pin "A") (pinfunction "A_A") (pintype "passive"))
    )
    (net (code "35") (name "Net-(D21-PadC)") (class "Default")
      (node (ref "D21") (pin "C") (pinfunction "C_C") (pintype "passive"))
      (node (ref "D24") (pin "A") (pinfunction "A_A") (pintype "passive"))
    )
    (net (code "36") (name "Net-(J3-A)") (class "Default")
      (node (ref "J3") (pin "2") (pinfunction "A_2") (pintype "passive"))
      (node (ref "U6") (pin "6") (pinfunction "Unlabeled_1_6") (pintype "passive"))
    )
    (net (code "37") (name "Net-(J3-B)") (class "Default")
      (node (ref "J3") (pin "3") (pinfunction "B_3") (pintype "passive"))
      (node (ref "U6") (pin "7") (pinfunction "Unlabeled_2_7") (pintype "passive"))
    )
    (net (code "38") (name "Net-(LED1-PadA)") (class "Default")
      (node (ref "LED1") (pin "A") (pinfunction "A_A") (pintype "passive"))
      (node (ref "R4") (pin "1") (pinfunction "1_1") (pintype "passive"))
    )
    (net (code "39") (name "Net-(LED2-PadA)") (class "Default")
      (node (ref "LED2") (pin "A") (pinfunction "A_A") (pintype "passive"))
      (node (ref "R8") (pin "1") (pinfunction "1_1") (pintype "passive"))
    )
    (net (code "40") (name "Net-(LED3-PadA)") (class "Default")
      (node (ref "LED3") (pin "A") (pinfunction "A_A") (pintype "passive"))
      (node (ref "R12") (pin "1") (pinfunction "1_1") (pintype "passive"))
    )
    (net (code "41") (name "Net-(LED4-PadA)") (class "Default")
      (node (ref "LED4") (pin "A") (pinfunction "A_A") (pintype "passive"))
      (node (ref "R22") (pin "1") (pinfunction "1_1") (pintype "passive"))
    )
    (net (code "42") (name "Net-(LED5-PadA)") (class "Default")
      (node (ref "LED5") (pin "A") (pinfunction "A_A") (pintype "passive"))
      (node (ref "R23") (pin "1") (pinfunction "1_1") (pintype "passive"))
    )
    (net (code "43") (name "Net-(LED6-PadA)") (class "Default")
      (node (ref "LED6") (pin "A") (pinfunction "A_A") (pintype "passive"))
      (node (ref "R24") (pin "1") (pinfunction "1_1") (pintype "passive"))
    )
    (net (code "44") (name "Net-(LVR1-ADJ)") (class "Default")
      (node (ref "LVR1") (pin "1") (pinfunction "ADJ_1") (pintype "power_in"))
      (node (ref "R13") (pin "2") (pinfunction "2_2") (pintype "passive"))
      (node (ref "R14") (pin "1") (pinfunction "1_1") (pintype "passive"))
    )
    (net (code "45") (name "Net-(LVR1-VI)") (class "Default")
      (node (ref "DP4") (pin "0") (pinfunction "0_0") (pintype "passive"))
      (node (ref "LVR1") (pin "3") (pinfunction "VI_3") (pintype "power_in"))
    )
    (net (code "46") (name "Net-(LVR1-VO)") (class "Default")
      (node (ref "LVR1") (pin "2") (pinfunction "VO_2") (pintype "power_in"))
      (node (ref "LVR2") (pin "3") (pinfunction "VI_3") (pintype "power_in"))
      (node (ref "R14") (pin "2") (pinfunction "2_2") (pintype "passive"))
    )
    (net (code "47") (name "Net-(LVR2-VO)") (class "Default")
      (node (ref "LVR2") (pin "2") (pinfunction "VO_2") (pintype "power_in"))
      (node (ref "R15") (pin "1") (pinfunction "1_1") (pintype "passive"))
    )
    (net (code "48") (name "Net-(LVR3-ADJ)") (class "Default")
      (node (ref "DP11") (pin "0") (pinfunction "0_0") (pintype "passive"))
      (node (ref "DP6") (pin "0") (pinfunction "0_0") (pintype "passive"))
      (node (ref "DP9") (pin "0") (pinfunction "0_0") (pintype "passive"))
      (node (ref "LVR3") (pin "1") (pinfunction "ADJ_1") (pintype "power_in"))
      (node (ref "R16") (pin "2") (pinfunction "2_2") (pintype "passive"))
      (node (ref "R19") (pin "2") (pinfunction "2_2") (pintype "passive"))
      (node (ref "R28") (pin "2") (pinfunction "2_2") (pintype "passive"))
      (node (ref "T4") (pin "1") (pinfunction "E_1") (pintype "passive"))
    )
    (net (code "49") (name "Net-(LVR3-VI)") (class "Default")
      (node (ref "LVR3") (pin "3") (pinfunction "VI_3") (pintype "power_in"))
      (node (ref "LVR4") (pin "2") (pinfunction "VO_2") (pintype "power_in"))
      (node (ref "R29") (pin "2") (pinfunction "2_2") (pintype "passive"))
    )
    (net (code "50") (name "Net-(LVR3-VO)") (class "Default")
      (node (ref "LVR3") (pin "2") (pinfunction "VO_2") (pintype "power_in"))
      (node (ref "R28") (pin "1") (pinfunction "1_1") (pintype "passive"))
    )
    (net (code "51") (name "Net-(LVR4-ADJ)") (class "Default")
      (node (ref "LVR4") (pin "1") (pinfunction "ADJ_1") (pintype "power_in"))
      (node (ref "R29") (pin "1") (pinfunction "1_1") (pintype "passive"))
      (node (ref "R30") (pin "2") (pinfunction "2_2") (pintype "passive"))
    )
    (net (code "52") (name "Net-(LVR4-VI)") (class "Default")
      (node (ref "DP10") (pin "0") (pinfunction "0_0") (pintype "passive"))
      (node (ref "LVR4") (pin "3") (pinfunction "VI_3") (pintype "power_in"))
    )
    (net (code "53") (name "Net-(T1-C)") (class "Default")
      (node (ref "D1") (pin "A") (pinfunction "A_A") (pintype "passive"))
      (node (ref "R4") (pin "2") (pinfunction "2_2") (pintype "passive"))
      (node (ref "T1") (pin "2") (pinfunction "C_2") (pintype "passive"))
    )
    (net (code "54") (name "Net-(T2-C)") (class "Default")
      (node (ref "D5") (pin "A") (pinfunction "A_A") (pintype "passive"))
      (node (ref "R8") (pin "2") (pinfunction "2_2") (pintype "passive"))
      (node (ref "T2") (pin "2") (pinfunction "C_2") (pintype "passive"))
    )
    (net (code "55") (name "Net-(T2-E)") (class "Default")
      (node (ref "COMP1") (pin "6") (pinfunction "ANODE_6") (pintype "bidirectional"))
      (node (ref "D4") (pin "C") (pinfunction "C_C") (pintype "passive"))
      (node (ref "DP1") (pin "1") (pinfunction "1_1") (pintype "passive"))
      (node (ref "DP2") (pin "0") (pinfunction "0_0") (pintype "passive"))
      (node (ref "LED1") (pin "C") (pinfunction "C_C") (pintype "passive"))
      (node (ref "R6") (pin "2") (pinfunction "2_2") (pintype "passive"))
      (node (ref "R7") (pin "2") (pinfunction "2_2") (pintype "passive"))
      (node (ref "T2") (pin "1") (pinfunction "E_1") (pintype "passive"))
      (node (ref "VR1") (pin "1") (pinfunction "CCW_1") (pintype "passive"))
      (node (ref "VR1") (pin "2") (pinfunction "WIPER_2") (pintype "passive"))
    )
    (net (code "56") (name "Net-(T3-C)") (class "Default")
      (node (ref "D9") (pin "A") (pinfunction "A_A") (pintype "passive"))
      (node (ref "R12") (pin "2") (pinfunction "2_2") (pintype "passive"))
      (node (ref "T3") (pin "2") (pinfunction "C_2") (pintype "passive"))
    )
    (net (code "57") (name "Net-(T3-E)") (class "Default")
      (node (ref "COMP2") (pin "6") (pinfunction "ANODE_6") (pintype "bidirectional"))
      (node (ref "D8") (pin "C") (pinfunction "C_C") (pintype "passive"))
      (node (ref "DP2") (pin "1") (pinfunction "1_1") (pintype "passive"))
      (node (ref "DP3") (pin "0") (pinfunction "0_0") (pintype "passive"))
      (node (ref "LED2") (pin "C") (pinfunction "C_C") (pintype "passive"))
      (node (ref "R11") (pin "2") (pinfunction "2_2") (pintype "passive"))
      (node (ref "R9") (pin "2") (pinfunction "2_2") (pintype "passive"))
      (node (ref "T3") (pin "1") (pinfunction "E_1") (pintype "passive"))
      (node (ref "VR2") (pin "1") (pinfunction "CCW_1") (pintype "passive"))
      (node (ref "VR2") (pin "2") (pinfunction "WIPER_2") (pintype "passive"))
    )
    (net (code "58") (name "Net-(T4-C)") (class "Default")
      (node (ref "D13") (pin "A") (pinfunction "A_A") (pintype "passive"))
      (node (ref "R22") (pin "2") (pinfunction "2_2") (pintype "passive"))
      (node (ref "T4") (pin "2") (pinfunction "C_2") (pintype "passive"))
    )
    (net (code "59") (name "Net-(T5-C)") (class "Default")
      (node (ref "D15") (pin "A") (pinfunction "A_A") (pintype "passive"))
      (node (ref "R23") (pin "2") (pinfunction "2_2") (pintype "passive"))
      (node (ref "T5") (pin "2") (pinfunction "C_2") (pintype "passive"))
    )
    (net (code "60") (name "Net-(T5-E)") (class "Default")
      (node (ref "COMP4") (pin "6") (pinfunction "ANODE_6") (pintype "bidirectional"))
      (node (ref "D22") (pin "C") (pinfunction "C_C") (pintype "passive"))
      (node (ref "DP6") (pin "1") (pinfunction "1_1") (pintype "passive"))
      (node (ref "DP7") (pin "0") (pinfunction "0_0") (pintype "passive"))
      (node (ref "LED4") (pin "C") (pinfunction "C_C") (pintype "passive"))
      (node (ref "R17") (pin "2") (pinfunction "2_2") (pintype "passive"))
      (node (ref "R20") (pin "2") (pinfunction "2_2") (pintype "passive"))
      (node (ref "T5") (pin "1") (pinfunction "E_1") (pintype "passive"))
      (node (ref "VR4") (pin "1") (pinfunction "CCW_1") (pintype "passive"))
      (node (ref "VR4") (pin "2") (pinfunction "WIPER_2") (pintype "passive"))
    )
    (net (code "61") (name "Net-(T6-C)") (class "Default")
      (node (ref "D14") (pin "A") (pinfunction "A_A") (pintype "passive"))
      (node (ref "R24") (pin "2") (pinfunction "2_2") (pintype "passive"))
      (node (ref "T6") (pin "2") (pinfunction "C_2") (pintype "passive"))
    )
    (net (code "62") (name "Net-(T6-E)") (class "Default")
      (node (ref "COMP5") (pin "6") (pinfunction "ANODE_6") (pintype "bidirectional"))
      (node (ref "D23") (pin "C") (pinfunction "C_C") (pintype "passive"))
      (node (ref "DP7") (pin "1") (pinfunction "1_1") (pintype "passive"))
      (node (ref "DP8") (pin "0") (pinfunction "0_0") (pintype "passive"))
      (node (ref "LED5") (pin "C") (pinfunction "C_C") (pintype "passive"))
      (node (ref "R18") (pin "2") (pinfunction "2_2") (pintype "passive"))
      (node (ref "R21") (pin "2") (pinfunction "2_2") (pintype "passive"))
      (node (ref "T6") (pin "1") (pinfunction "E_1") (pintype "passive"))
      (node (ref "VR5") (pin "1") (pinfunction "CCW_1") (pintype "passive"))
      (node (ref "VR5") (pin "2") (pinfunction "WIPER_2") (pintype "passive"))
    )
    (net (code "63") (name "Net-(U1-GPIO2{slash}SDA1)") (class "Default")
      (node (ref "U1") (pin "3") (pinfunction "GPIO2/SDA1_3") (pintype "bidirectional"))
      (node (ref "U4") (pin "1") (pinfunction "SDA_1") (pintype "passive"))
      (node (ref "U5") (pin "0") (pinfunction "LV4_0") (pintype "passive"))
    )
    (net (code "64") (name "Net-(U1-GPIO3{slash}SCL1)") (class "Default")
      (node (ref "U1") (pin "5") (pinfunction "GPIO3/SCL1_5") (pintype "bidirectional"))
      (node (ref "U4") (pin "0") (pinfunction "SCL_0") (pintype "passive"))
      (node (ref "U5") (pin "1") (pinfunction "LV3_1") (pintype "passive"))
    )
    (net (code "65") (name "Net-(U1-GPIO4{slash}GPIO_GCKL)") (class "Default")
      (node (ref "U1") (pin "7") (pinfunction "GPIO4/GPIO_GCKL_7") (pintype "bidirectional"))
      (node (ref "U2") (pin "4") (pinfunction "PUL_(+)_4") (pintype "passive"))
    )
    (net (code "66") (name "Net-(U1-GPIO17{slash}GPIO_GEN0)") (class "Default")
      (node (ref "U1") (pin "11") (pinfunction "GPIO17/GPIO_GEN0_11") (pintype "bidirectional"))
      (node (ref "U2") (pin "2") (pinfunction "DIR_(+)_2") (pintype "passive"))
    )
    (net (code "67") (name "Net-(U1-GPIO22{slash}GPIO_GEN3)") (class "Default")
      (node (ref "U1") (pin "15") (pinfunction "GPIO22/GPIO_GEN3_15") (pintype "bidirectional"))
      (node (ref "U3") (pin "2") (pinfunction "DIR_(+)_2") (pintype "passive"))
    )
    (net (code "68") (name "Net-(U1-GPIO27{slash}GPIO_GEN2)") (class "Default")
      (node (ref "U1") (pin "13") (pinfunction "GPIO27/GPIO_GEN2_13") (pintype "bidirectional"))
      (node (ref "U3") (pin "4") (pinfunction "PUL_(+)_4") (pintype "passive"))
    )
    (net (code "69") (name "Net-(U5-HV3)") (class "Default")
      (node (ref "U5") (pin "7") (pinfunction "HV3_7") (pintype "passive"))
      (node (ref "U6") (pin "4") (pinfunction "SDA_4") (pintype "passive"))
    )
    (net (code "70") (name "Net-(U5-HV4)") (class "Default")
      (node (ref "U5") (pin "6") (pinfunction "HV4_6") (pintype "passive"))
      (node (ref "U6") (pin "3") (pinfunction "SCL_3") (pintype "passive"))
    )
    (net (code "71") (name "Net-(VR1-CW)") (class "Default")
      (node (ref "R2") (pin "1") (pinfunction "1_1") (pintype "passive"))
      (node (ref "VR1") (pin "3") (pinfunction "CW_3") (pintype "passive"))
    )
    (net (code "72") (name "Net-(VR2-CW)") (class "Default")
      (node (ref "R5") (pin "1") (pinfunction "1_1") (pintype "passive"))
      (node (ref "VR2") (pin "3") (pinfunction "CW_3") (pintype "passive"))
    )
    (net (code "73") (name "Net-(VR3-CW)") (class "Default")
      (node (ref "R10") (pin "1") (pinfunction "1_1") (pintype "passive"))
      (node (ref "VR3") (pin "3") (pinfunction "CW_3") (pintype "passive"))
    )
    (net (code "74") (name "Net-(VR4-CW)") (class "Default")
      (node (ref "R25") (pin "1") (pinfunction "1_1") (pintype "passive"))
      (node (ref "VR4") (pin "3") (pinfunction "CW_3") (pintype "passive"))
    )
    (net (code "75") (name "Net-(VR5-CW)") (class "Default")
      (node (ref "R26") (pin "1") (pinfunction "1_1") (pintype "passive"))
      (node (ref "VR5") (pin "3") (pinfunction "CW_3") (pintype "passive"))
    )
    (net (code "76") (name "Net-(VR6-CW)") (class "Default")
      (node (ref "R27") (pin "1") (pinfunction "1_1") (pintype "passive"))
      (node (ref "VR6") (pin "3") (pinfunction "CW_3") (pintype "passive"))
    )
    (net (code "77") (name "unconnected-(COMP1-ANODE-Pad2)") (class "Default")
      (node (ref "COMP1") (pin "2") (pinfunction "ANODE_2") (pintype "bidirectional+no_connect"))
    )
    (net (code "78") (name "unconnected-(COMP1-ANODE-Pad3)") (class "Default")
      (node (ref "COMP1") (pin "3") (pinfunction "ANODE_3") (pintype "bidirectional+no_connect"))
    )
    (net (code "79") (name "unconnected-(COMP1-ANODE-Pad7)") (class "Default")
      (node (ref "COMP1") (pin "7") (pinfunction "ANODE_7") (pintype "bidirectional+no_connect"))
    )
    (net (code "80") (name "unconnected-(COMP2-ANODE-Pad2)") (class "Default")
      (node (ref "COMP2") (pin "2") (pinfunction "ANODE_2") (pintype "bidirectional+no_connect"))
    )
    (net (code "81") (name "unconnected-(COMP2-ANODE-Pad3)") (class "Default")
      (node (ref "COMP2") (pin "3") (pinfunction "ANODE_3") (pintype "bidirectional+no_connect"))
    )
    (net (code "82") (name "unconnected-(COMP2-ANODE-Pad7)") (class "Default")
      (node (ref "COMP2") (pin "7") (pinfunction "ANODE_7") (pintype "bidirectional+no_connect"))
    )
    (net (code "83") (name "unconnected-(COMP3-ANODE-Pad2)") (class "Default")
      (node (ref "COMP3") (pin "2") (pinfunction "ANODE_2") (pintype "bidirectional+no_connect"))
    )
    (net (code "84") (name "unconnected-(COMP3-ANODE-Pad3)") (class "Default")
      (node (ref "COMP3") (pin "3") (pinfunction "ANODE_3") (pintype "bidirectional+no_connect"))
    )
    (net (code "85") (name "unconnected-(COMP3-ANODE-Pad7)") (class "Default")
      (node (ref "COMP3") (pin "7") (pinfunction "ANODE_7") (pintype "bidirectional+no_connect"))
    )
    (net (code "86") (name "unconnected-(COMP4-ANODE-Pad2)") (class "Default")
      (node (ref "COMP4") (pin "2") (pinfunction "ANODE_2") (pintype "bidirectional+no_connect"))
    )
    (net (code "87") (name "unconnected-(COMP4-ANODE-Pad3)") (class "Default")
      (node (ref "COMP4") (pin "3") (pinfunction "ANODE_3") (pintype "bidirectional+no_connect"))
    )
    (net (code "88") (name "unconnected-(COMP4-ANODE-Pad7)") (class "Default")
      (node (ref "COMP4") (pin "7") (pinfunction "ANODE_7") (pintype "bidirectional+no_connect"))
    )
    (net (code "89") (name "unconnected-(COMP5-ANODE-Pad2)") (class "Default")
      (node (ref "COMP5") (pin "2") (pinfunction "ANODE_2") (pintype "bidirectional+no_connect"))
    )
    (net (code "90") (name "unconnected-(COMP5-ANODE-Pad3)") (class "Default")
      (node (ref "COMP5") (pin "3") (pinfunction "ANODE_3") (pintype "bidirectional+no_connect"))
    )
    (net (code "91") (name "unconnected-(COMP5-ANODE-Pad7)") (class "Default")
      (node (ref "COMP5") (pin "7") (pinfunction "ANODE_7") (pintype "bidirectional+no_connect"))
    )
    (net (code "92") (name "unconnected-(COMP6-ANODE-Pad2)") (class "Default")
      (node (ref "COMP6") (pin "2") (pinfunction "ANODE_2") (pintype "bidirectional+no_connect"))
    )
    (net (code "93") (name "unconnected-(COMP6-ANODE-Pad3)") (class "Default")
      (node (ref "COMP6") (pin "3") (pinfunction "ANODE_3") (pintype "bidirectional+no_connect"))
    )
    (net (code "94") (name "unconnected-(COMP6-ANODE-Pad7)") (class "Default")
      (node (ref "COMP6") (pin "7") (pinfunction "ANODE_7") (pintype "bidirectional+no_connect"))
    )
    (net (code "95") (name "unconnected-(U1-3V3-Pad1)") (class "Default")
      (node (ref "U1") (pin "1") (pinfunction "3V3_1") (pintype "power_in"))
    )
    (net (code "96") (name "unconnected-(U1-3V3-Pad17)") (class "Default")
      (node (ref "U1") (pin "17") (pinfunction "3V3_17") (pintype "power_in"))
    )
    (net (code "97") (name "unconnected-(U1-5V0-Pad2)") (class "Default")
      (node (ref "U1") (pin "2") (pinfunction "5V0_2") (pintype "power_in"))
    )
    (net (code "98") (name "unconnected-(U1-5V0-Pad4)") (class "Default")
      (node (ref "U1") (pin "4") (pinfunction "5V0_4") (pintype "power_in"))
    )
    (net (code "99") (name "unconnected-(U1-GND-Pad6)") (class "Default")
      (node (ref "U1") (pin "6") (pinfunction "GND_6") (pintype "power_in"))
    )
    (net (code "100") (name "unconnected-(U1-GND-Pad9)") (class "Default")
      (node (ref "U1") (pin "9") (pinfunction "GND_9") (pintype "power_in"))
    )
    (net (code "101") (name "unconnected-(U1-GND-Pad14)") (class "Default")
      (node (ref "U1") (pin "14") (pinfunction "GND_14") (pintype "power_in"))
    )
    (net (code "102") (name "unconnected-(U1-GND-Pad20)") (class "Default")
      (node (ref "U1") (pin "20") (pinfunction "GND_20") (pintype "power_in"))
    )
    (net (code "103") (name "unconnected-(U1-GND-Pad25)") (class "Default")
      (node (ref "U1") (pin "25") (pinfunction "GND_25") (pintype "power_in"))
    )
    (net (code "104") (name "unconnected-(U1-GND-Pad30)") (class "Default")
      (node (ref "U1") (pin "30") (pinfunction "GND_30") (pintype "power_in"))
    )
    (net (code "105") (name "unconnected-(U1-GND-Pad34)") (class "Default")
      (node (ref "U1") (pin "34") (pinfunction "GND_34") (pintype "power_in"))
    )
    (net (code "106") (name "unconnected-(U1-GND-Pad39)") (class "Default")
      (node (ref "U1") (pin "39") (pinfunction "GND_39") (pintype "power_in"))
    )
    (net (code "107") (name "unconnected-(U1-GPIO5-Pad29)") (class "Default")
      (node (ref "U1") (pin "29") (pinfunction "GPIO5_29") (pintype "bidirectional"))
    )
    (net (code "108") (name "unconnected-(U1-GPIO6-Pad31)") (class "Default")
      (node (ref "U1") (pin "31") (pinfunction "GPIO6_31") (pintype "bidirectional"))
    )
    (net (code "109") (name "unconnected-(U1-GPIO7{slash}!SPI_CE1!-Pad26)") (class "Default")
      (node (ref "U1") (pin "26") (pinfunction "GPIO7/!SPI_CE1!_26") (pintype "bidirectional"))
    )
    (net (code "110") (name "unconnected-(U1-GPIO8{slash}!SPI_CE0!-Pad24)") (class "Default")
      (node (ref "U1") (pin "24") (pinfunction "GPIO8/!SPI_CE0!_24") (pintype "bidirectional"))
    )
    (net (code "111") (name "unconnected-(U1-GPIO9{slash}SPI_MISO-Pad21)") (class "Default")
      (node (ref "U1") (pin "21") (pinfunction "GPIO9/SPI_MISO_21") (pintype "bidirectional"))
    )
    (net (code "112") (name "unconnected-(U1-GPIO10{slash}SPI_MOSI-Pad19)") (class "Default")
      (node (ref "U1") (pin "19") (pinfunction "GPIO10/SPI_MOSI_19") (pintype "bidirectional"))
    )
    (net (code "113") (name "unconnected-(U1-GPIO11{slash}SPI_SCLK-Pad23)") (class "Default")
      (node (ref "U1") (pin "23") (pinfunction "GPIO11/SPI_SCLK_23") (pintype "bidirectional"))
    )
    (net (code "114") (name "unconnected-(U1-GPIO12-Pad32)") (class "Default")
      (node (ref "U1") (pin "32") (pinfunction "GPIO12_32") (pintype "bidirectional"))
    )
    (net (code "115") (name "unconnected-(U1-GPIO13-Pad33)") (class "Default")
      (node (ref "U1") (pin "33") (pinfunction "GPIO13_33") (pintype "bidirectional"))
    )
    (net (code "116") (name "unconnected-(U1-GPIO16-Pad36)") (class "Default")
      (node (ref "U1") (pin "36") (pinfunction "GPIO16_36") (pintype "bidirectional"))
    )
    (net (code "117") (name "unconnected-(U1-GPIO18{slash}GPIO_GEN1-Pad12)") (class "Default")
      (node (ref "U1") (pin "12") (pinfunction "GPIO18/GPIO_GEN1_12") (pintype "bidirectional"))
    )
    (net (code "118") (name "unconnected-(U1-GPIO19-Pad35)") (class "Default")
      (node (ref "U1") (pin "35") (pinfunction "GPIO19_35") (pintype "bidirectional"))
    )
    (net (code "119") (name "unconnected-(U1-GPIO20-Pad38)") (class "Default")
      (node (ref "U1") (pin "38") (pinfunction "GPIO20_38") (pintype "bidirectional"))
    )
    (net (code "120") (name "unconnected-(U1-GPIO21-Pad40)") (class "Default")
      (node (ref "U1") (pin "40") (pinfunction "GPIO21_40") (pintype "bidirectional"))
    )
    (net (code "121") (name "unconnected-(U1-GPIO23{slash}GPIO_GEN4-Pad16)") (class "Default")
      (node (ref "U1") (pin "16") (pinfunction "GPIO23/GPIO_GEN4_16") (pintype "bidirectional"))
    )
    (net (code "122") (name "unconnected-(U1-GPIO24{slash}GPIO_GEN5-Pad18)") (class "Default")
      (node (ref "U1") (pin "18") (pinfunction "GPIO24/GPIO_GEN5_18") (pintype "bidirectional"))
    )
    (net (code "123") (name "unconnected-(U1-GPIO25{slash}GPIO_GEN6-Pad22)") (class "Default")
      (node (ref "U1") (pin "22") (pinfunction "GPIO25/GPIO_GEN6_22") (pintype "bidirectional"))
    )
    (net (code "124") (name "unconnected-(U1-GPIO26-Pad37)") (class "Default")
      (node (ref "U1") (pin "37") (pinfunction "GPIO26_37") (pintype "bidirectional"))
    )
    (net (code "125") (name "unconnected-(U1-ID_SC-Pad28)") (class "Default")
      (node (ref "U1") (pin "28") (pinfunction "ID_SC_28") (pintype "bidirectional"))
    )
    (net (code "126") (name "unconnected-(U1-ID_SD-Pad27)") (class "Default")
      (node (ref "U1") (pin "27") (pinfunction "ID_SD_27") (pintype "bidirectional"))
    )
    (net (code "127") (name "unconnected-(U1-RXD0{slash}GPIO15-Pad10)") (class "Default")
      (node (ref "U1") (pin "10") (pinfunction "RXD0/GPIO15_10") (pintype "bidirectional"))
    )
    (net (code "128") (name "unconnected-(U1-SHIELD-PadS1)") (class "Default")
      (node (ref "U1") (pin "S1") (pinfunction "SHIELD_S1") (pintype "power_in"))
    )
    (net (code "129") (name "unconnected-(U1-SHIELD-PadS2)") (class "Default")
      (node (ref "U1") (pin "S2") (pinfunction "SHIELD_S2") (pintype "power_in"))
    )
    (net (code "130") (name "unconnected-(U1-SHIELD-PadS3)") (class "Default")
      (node (ref "U1") (pin "S3") (pinfunction "SHIELD_S3") (pintype "power_in"))
    )
    (net (code "131") (name "unconnected-(U1-SHIELD-PadS4)") (class "Default")
      (node (ref "U1") (pin "S4") (pinfunction "SHIELD_S4") (pintype "power_in"))
    )
    (net (code "132") (name "unconnected-(U1-TXD0{slash}GPIO14-Pad8)") (class "Default")
      (node (ref "U1") (pin "8") (pinfunction "TXD0/GPIO14_8") (pintype "bidirectional"))
    )
    (net (code "133") (name "unconnected-(U4-3v3-Pad7)") (class "Default")
      (node (ref "U4") (pin "7") (pinfunction "3v3_7") (pintype "passive+no_connect"))
    )
    (net (code "134") (name "unconnected-(U4-DRDY-Pad4)") (class "Default")
      (node (ref "U4") (pin "4") (pinfunction "DRDY_4") (pintype "passive+no_connect"))
    )
    (net (code "135") (name "unconnected-(U4-I1-Pad3)") (class "Default")
      (node (ref "U4") (pin "3") (pinfunction "I1_3") (pintype "passive+no_connect"))
    )
    (net (code "136") (name "unconnected-(U4-I2-Pad2)") (class "Default")
      (node (ref "U4") (pin "2") (pinfunction "I2_2") (pintype "passive+no_connect"))
    )
    (net (code "137") (name "unconnected-(U5-HV1-Pad11)") (class "Default")
      (node (ref "U5") (pin "11") (pinfunction "HV1_11") (pintype "passive+no_connect"))
    )
    (net (code "138") (name "unconnected-(U5-HV2-Pad10)") (class "Default")
      (node (ref "U5") (pin "10") (pinfunction "HV2_10") (pintype "passive+no_connect"))
    )
    (net (code "139") (name "unconnected-(U5-LV1-Pad5)") (class "Default")
      (node (ref "U5") (pin "5") (pinfunction "LV1_5") (pintype "passive+no_connect"))
    )
    (net (code "140") (name "unconnected-(U5-LV2-Pad4)") (class "Default")
      (node (ref "U5") (pin "4") (pinfunction "LV2_4") (pintype "passive+no_connect"))
    )
    (net (code "141") (name "unconnected-(U6-3V-Pad1)") (class "Default")
      (node (ref "U6") (pin "1") (pinfunction "3V_1") (pintype "passive+no_connect"))
    )
    (net (code "142") (name "unconnected-(U6-INT-Pad5)") (class "Default")
      (node (ref "U6") (pin "5") (pinfunction "INT_5") (pintype "passive+no_connect"))
    )
    (net (code "143") (name "unconnected-(U6-Unlabeled_3-Pad8)") (class "Default")
      (node (ref "U6") (pin "8") (pinfunction "Unlabeled_3_8") (pintype "passive+no_connect"))
    )
    (net (code "144") (name "unconnected-(U7-3.3V-Pad8)") (class "Default")
      (node (ref "U7") (pin "8") (pinfunction "3.3V_8") (pintype "passive+no_connect"))
    )
    (net (code "145") (name "unconnected-(U7-En-Pad7)") (class "Default")
      (node (ref "U7") (pin "7") (pinfunction "En_7") (pintype "passive+no_connect"))
    )
    (net (code "146") (name "unconnected-(U7-Fix-Pad5)") (class "Default")
      (node (ref "U7") (pin "5") (pinfunction "Fix_5") (pintype "passive+no_connect"))
    )
    (net (code "147") (name "unconnected-(U7-GND-Pad2)") (class "Default")
      (node (ref "U7") (pin "2") (pinfunction "GND_2") (pintype "passive+no_connect"))
    )
    (net (code "148") (name "unconnected-(U7-PPS-Pad0)") (class "Default")
      (node (ref "U7") (pin "0") (pinfunction "PPS_0") (pintype "passive+no_connect"))
    )
    (net (code "149") (name "unconnected-(U7-Rx-Pad3)") (class "Default")
      (node (ref "U7") (pin "3") (pinfunction "Rx_3") (pintype "passive+no_connect"))
    )
    (net (code "150") (name "unconnected-(U7-Tx-Pad4)") (class "Default")
      (node (ref "U7") (pin "4") (pinfunction "Tx_4") (pintype "passive+no_connect"))
    )
    (net (code "151") (name "unconnected-(U7-Vbat-Pad6)") (class "Default")
      (node (ref "U7") (pin "6") (pinfunction "Vbat_6") (pintype "passive+no_connect"))
    )
    (net (code "152") (name "unconnected-(U7-Vin-Pad1)") (class "Default")
      (node (ref "U7") (pin "1") (pinfunction "Vin_1") (pintype "passive+no_connect"))
    )
    (net (code "153") (name "unconnected-(U8-Pad1)") (class "Default")
      (node (ref "U8") (pin "1") (pinfunction "1_1") (pintype "passive+no_connect"))
    )
    (net (code "154") (name "unconnected-(U8-Pad2)") (class "Default")
      (node (ref "U8") (pin "2") (pinfunction "2_2") (pintype "passive+no_connect"))
    )
    (net (code "155") (name "unconnected-(U8-Pad3)") (class "Default")
      (node (ref "U8") (pin "3") (pinfunction "3_3") (pintype "passive+no_connect"))
    )
    (net (code "156") (name "unconnected-(U8-Pad4)") (class "Default")
      (node (ref "U8") (pin "4") (pinfunction "4_4") (pintype "passive"))
    )
    (net (code "157") (name "unconnected-(U8-Pad5)") (class "Default")
      (node (ref "U8") (pin "5") (pinfunction "5_5") (pintype "passive+no_connect"))
    )
    (net (code "158") (name "unconnected-(U8-Pad6)") (class "Default")
      (node (ref "U8") (pin "6") (pinfunction "6_6") (pintype "passive+no_connect"))
    )
    (net (code "159") (name "unconnected-(U8-Pad7)") (class "Default")
      (node (ref "U8") (pin "7") (pinfunction "7_7") (pintype "passive+no_connect"))
    )
    (net (code "160") (name "unconnected-(U8-Pad8)") (class "Default")
      (node (ref "U8") (pin "8") (pinfunction "8_8") (pintype "passive+no_connect"))
    )
    (net (code "161") (name "unconnected-(U8-Pad9)") (class "Default")
      (node (ref "U8") (pin "9") (pinfunction "9_9") (pintype "passive+no_connect"))
    )
    (net (code "162") (name "unconnected-(U8-Pad10)") (class "Default")
      (node (ref "U8") (pin "10") (pinfunction "10_10") (pintype "passive+no_connect"))
    )
    (net (code "163") (name "unconnected-(U8-Pad11)") (class "Default")
      (node (ref "U8") (pin "11") (pinfunction "11_11") (pintype "passive+no_connect"))
    )
    (net (code "164") (name "unconnected-(U8-Pad12)") (class "Default")
      (node (ref "U8") (pin "12") (pinfunction "12_12") (pintype "passive+no_connect"))
    )
    (net (code "165") (name "unconnected-(U8-Pad13)") (class "Default")
      (node (ref "U8") (pin "13") (pinfunction "13_13") (pintype "passive+no_connect"))
    )
    (net (code "166") (name "unconnected-(U8-Pad14)") (class "Default")
      (node (ref "U8") (pin "14") (pinfunction "14_14") (pintype "passive+no_connect"))
    )
    (net (code "167") (name "unconnected-(U8-Pad15)") (class "Default")
      (node (ref "U8") (pin "15") (pinfunction "15_15") (pintype "passive+no_connect"))
    )
    (net (code "168") (name "unconnected-(U8-Pad16)") (class "Default")
      (node (ref "U8") (pin "16") (pinfunction "16_16") (pintype "passive+no_connect"))
    )
    (net (code "169") (name "unconnected-(U8-Pad17)") (class "Default")
      (node (ref "U8") (pin "17") (pinfunction "17_17") (pintype "passive+no_connect"))
    )
    (net (code "170") (name "unconnected-(U8-Pad18)") (class "Default")
      (node (ref "U8") (pin "18") (pinfunction "18_18") (pintype "passive+no_connect"))
    )
    (net (code "171") (name "unconnected-(U8-Pad19)") (class "Default")
      (node (ref "U8") (pin "19") (pinfunction "19_19") (pintype "passive+no_connect"))
    )
    (net (code "172") (name "unconnected-(U8-Pad20)") (class "Default")
      (node (ref "U8") (pin "20") (pinfunction "20_20") (pintype "passive+no_connect"))
    )
    (net (code "173") (name "unconnected-(U8-Pad21)") (class "Default")
      (node (ref "U8") (pin "21") (pinfunction "21_21") (pintype "passive+no_connect"))
    )
    (net (code "174") (name "unconnected-(U8-Pad22)") (class "Default")
      (node (ref "U8") (pin "22") (pinfunction "22_22") (pintype "passive+no_connect"))
    )
    (net (code "175") (name "unconnected-(U8-Pad23)") (class "Default")
      (node (ref "U8") (pin "23") (pinfunction "23_23") (pintype "passive+no_connect"))
    )
    (net (code "176") (name "unconnected-(U8-Pad24)") (class "Default")
      (node (ref "U8") (pin "24") (pinfunction "24_24") (pintype "passive+no_connect"))
    )
    (net (code "177") (name "unconnected-(U8-Pad25)") (class "Default")
      (node (ref "U8") (pin "25") (pinfunction "25_25") (pintype "passive+no_connect"))
    )
    (net (code "178") (name "unconnected-(U8-Pad26)") (class "Default")
      (node (ref "U8") (pin "26") (pinfunction "26_26") (pintype "passive+no_connect"))
    )
    (net (code "179") (name "unconnected-(U8-Pad27)") (class "Default")
      (node (ref "U8") (pin "27") (pinfunction "27_27") (pintype "passive+no_connect"))
    )
    (net (code "180") (name "unconnected-(U8-Pad28)") (class "Default")
      (node (ref "U8") (pin "28") (pinfunction "28_28") (pintype "passive+no_connect"))
    )
  )
)
